# Preamplifier_switch.net
KiCad netlist of a schematic drawn in Altium Designer
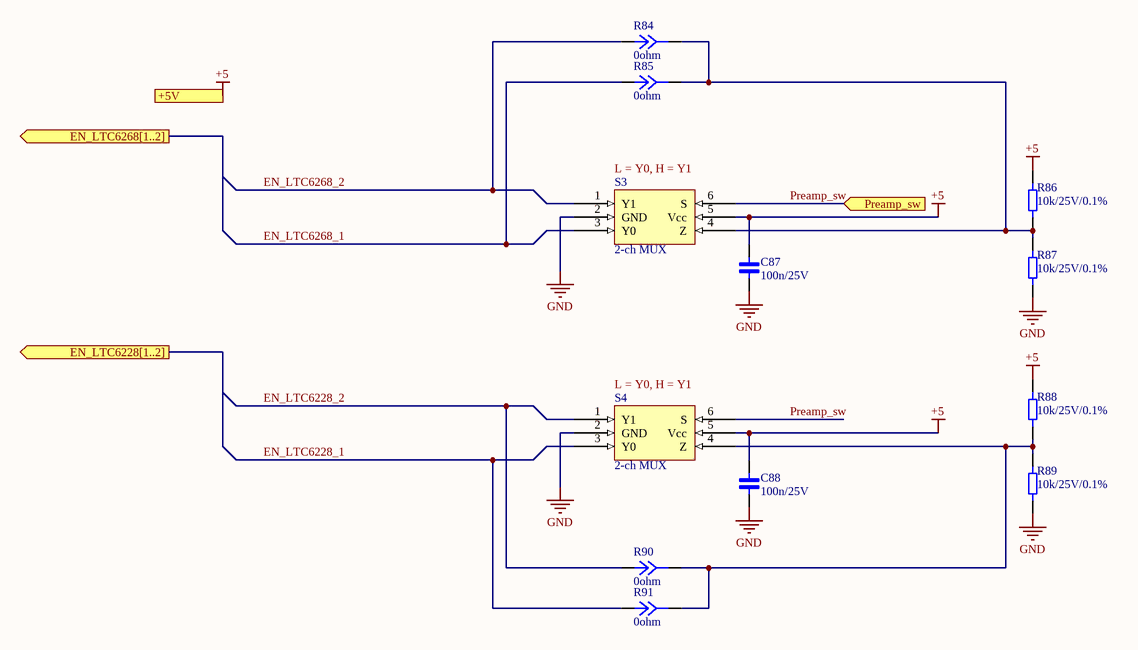
[diagram p0: Preamplifier_switch.SchDoc]

(export (version "E")
  (design (tool "Eeschema 10.0.6"))
  (components
    (comp (ref "C87")
      (value "100n/25V")
      (footprint "CAP_0603")
      (description "Ceramic Capacitor 100n / 0603 / 25V / ±5%, Wurth Elektronik MLCC")
      (libsource (lib "Cubesat_lib") (part "Cap_0603_100n"))
    )
    (comp (ref "C88")
      (value "100n/25V")
      (footprint "CAP_0603")
      (description "Ceramic Capacitor 100n / 0603 / 25V / ±5%, Wurth Elektronik MLCC")
      (libsource (lib "Cubesat_lib") (part "Cap_0603_100n"))
    )
    (comp (ref "R84") (value "0ohm") (footprint "Jumper") (libsource (lib "Cubesat_lib") (part "Jumper")))
    (comp (ref "R85") (value "0ohm") (footprint "Jumper") (libsource (lib "Cubesat_lib") (part "Jumper")))
    (comp (ref "R86")
      (value "10k/25V/0.1%")
      (footprint "RES_0603")
      (description "Vishay, thin film resistor 10k/25V/0.1%")
      (libsource (lib "") (part "Res_0603_10k_1"))
    )
    (comp (ref "R87")
      (value "10k/25V/0.1%")
      (footprint "RES_0603")
      (description "Vishay, thin film resistor 10k/25V/0.1%")
      (libsource (lib "Cubesat_lib") (part "Res_0603_10k"))
    )
    (comp (ref "R88")
      (value "10k/25V/0.1%")
      (footprint "RES_0603")
      (description "Vishay, thin film resistor 10k/25V/0.1%")
      (libsource (lib "Cubesat_lib") (part "Res_0603_10k"))
    )
    (comp (ref "R89")
      (value "10k/25V/0.1%")
      (footprint "RES_0603")
      (description "Vishay, thin film resistor 10k/25V/0.1%")
      (libsource (lib "Cubesat_lib") (part "Res_0603_10k"))
    )
    (comp (ref "R90") (value "0ohm") (footprint "Jumper") (libsource (lib "Cubesat_lib") (part "Jumper")))
    (comp (ref "R91") (value "0ohm") (footprint "Jumper") (libsource (lib "Cubesat_lib") (part "Jumper")))
    (comp (ref "S3")
      (value "2-ch MUX")
      (footprint "TSOP6")
      (description "2-channel analog multiplexer/demultiplexernexperia")
      (libsource (lib "Cubesat_lib") (part "74LVC1G3157-Q100"))
    )
    (comp (ref "S4")
      (value "2-ch MUX")
      (footprint "TSOP6")
      (description "2-channel analog multiplexer/demultiplexernexperia")
      (libsource (lib "Cubesat_lib") (part "74LVC1G3157-Q100"))
    )
  )
  (nets
    (net (code "5") (name "+5") (class "Default")
      (node (ref "C87") (pin "2") (pinfunction "2_2") (pintype "passive"))
      (node (ref "C88") (pin "2") (pinfunction "2_2") (pintype "passive"))
      (node (ref "R86") (pin "2") (pinfunction "2_2") (pintype "passive"))
      (node (ref "R88") (pin "2") (pinfunction "2_2") (pintype "passive"))
      (node (ref "S3") (pin "5") (pinfunction "Vcc_5") (pintype "input"))
      (node (ref "S4") (pin "5") (pinfunction "Vcc_5") (pintype "input"))
    )
    (net (code "7") (name "/EN_LTC6228_1") (class "Default")
      (node (ref "R91") (pin "2") (pinfunction "2_2") (pintype "passive"))
      (node (ref "S4") (pin "3") (pinfunction "Y0_3") (pintype "input"))
    )
    (net (code "8") (name "/EN_LTC6228_2") (class "Default")
      (node (ref "R90") (pin "2") (pinfunction "2_2") (pintype "passive"))
      (node (ref "S4") (pin "1") (pinfunction "Y1_1") (pintype "input"))
    )
    (net (code "10") (name "/EN_LTC6268_1") (class "Default")
      (node (ref "R85") (pin "2") (pinfunction "2_2") (pintype "passive"))
      (node (ref "S3") (pin "3") (pinfunction "Y0_3") (pintype "input"))
    )
    (net (code "11") (name "/EN_LTC6268_2") (class "Default")
      (node (ref "R84") (pin "2") (pinfunction "2_2") (pintype "passive"))
      (node (ref "S3") (pin "1") (pinfunction "Y1_1") (pintype "input"))
    )
    (net (code "12") (name "/Preamp_sw") (class "Default")
      (node (ref "S3") (pin "6") (pinfunction "S_6") (pintype "input"))
      (node (ref "S4") (pin "6") (pinfunction "S_6") (pintype "input"))
    )
    (net (code "13") (name "GND") (class "Default")
      (node (ref "C87") (pin "1") (pinfunction "1_1") (pintype "passive"))
      (node (ref "C88") (pin "1") (pinfunction "1_1") (pintype "passive"))
      (node (ref "R87") (pin "2") (pinfunction "2_2") (pintype "passive"))
      (node (ref "R89") (pin "2") (pinfunction "2_2") (pintype "passive"))
      (node (ref "S3") (pin "2") (pinfunction "GND_2") (pintype "input"))
      (node (ref "S4") (pin "2") (pinfunction "GND_2") (pintype "input"))
    )
    (net (code "14") (name "Net-(S3-Z)") (class "Default")
      (node (ref "R84") (pin "2") (pinfunction "2_2") (pintype "passive"))
      (node (ref "R85") (pin "2") (pinfunction "2_2") (pintype "passive"))
      (node (ref "R86") (pin "2") (pinfunction "2_2") (pintype "passive"))
      (node (ref "R87") (pin "2") (pinfunction "2_2") (pintype "passive"))
      (node (ref "S3") (pin "4") (pinfunction "Z_4") (pintype "input"))
    )
    (net (code "15") (name "Net-(S4-Z)") (class "Default")
      (node (ref "R88") (pin "2") (pinfunction "2_2") (pintype "passive"))
      (node (ref "R89") (pin "2") (pinfunction "2_2") (pintype "passive"))
      (node (ref "R90") (pin "2") (pinfunction "2_2") (pintype "passive"))
      (node (ref "R91") (pin "2") (pinfunction "2_2") (pintype "passive"))
      (node (ref "S4") (pin "4") (pinfunction "Z_4") (pintype "input"))
    )
  )
)
